# VC02.net
KiCad netlist of a schematic drawn in EAGLE
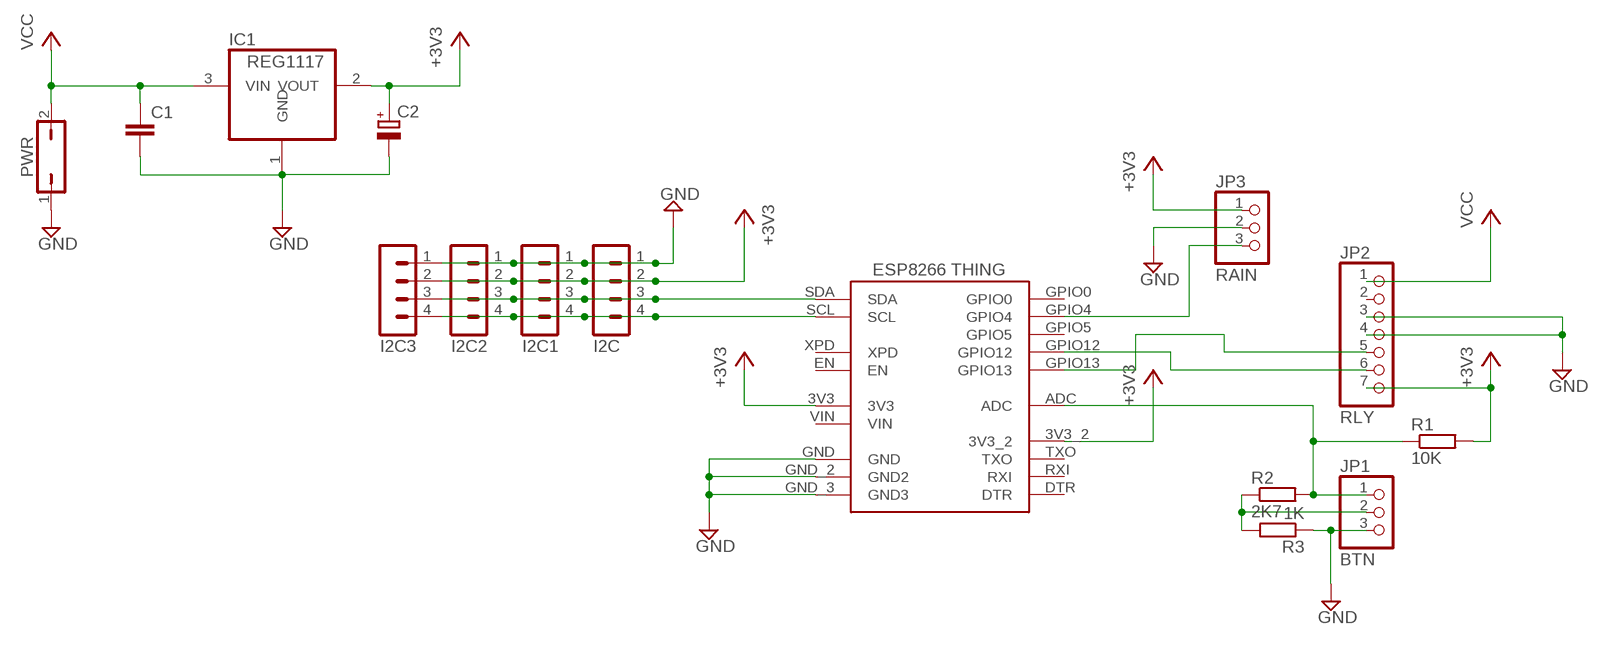
[diagram p0: schematic, sheet 1]

(export (version "E")
  (design (tool "Eeschema 10.0.6"))
  (components
    (comp (ref "C1")
      (value "C-EUC0603K")
      (footprint "eagle-import:C0603K")
      (fields (field (name "MF") "AVX") (field (name "MPN") "0603YC104K4T2A"))
      (libsource (lib "eagle-import") (part "C-EUC0603K"))
    )
    (comp (ref "C2")
      (value "CPOL-EUB")
      (footprint "eagle-import:PANASONIC_B")
      (fields (field (name "MF") "PANASONIC ELECTRONIC COMPONENTS") (field (name "MPN") "EEEFC1C220AR"))
      (libsource (lib "eagle-import") (part "CPOL-EUB"))
    )
    (comp (ref "I2C")
      (value "MA04-1")
      (footprint "eagle-import:MA04-1")
      (libsource (lib "eagle-import") (part "MA04-1"))
    )
    (comp (ref "I2C1")
      (value "MA04-1")
      (footprint "eagle-import:MA04-1")
      (libsource (lib "eagle-import") (part "MA04-1"))
    )
    (comp (ref "I2C2")
      (value "MA04-1")
      (footprint "eagle-import:MA04-1")
      (libsource (lib "eagle-import") (part "MA04-1"))
    )
    (comp (ref "I2C3")
      (value "MA04-1")
      (footprint "eagle-import:MA04-1")
      (libsource (lib "eagle-import") (part "MA04-1"))
    )
    (comp (ref "IC1")
      (value "REG1117")
      (footprint "eagle-import:SOT223")
      (fields
        (field (name "MF") "STMICROELECTRONICS")
        (field (name "MPN") "LD1117S33TR")
        (field (name "OC_FARNELL") "1202826")
      )
      (libsource (lib "eagle-import") (part "REG1117"))
    )
    (comp (ref "JP1")
      (value "BTN")
      (footprint "eagle-import:1X03")
      (libsource (lib "eagle-import") (part "PINHD-1X3"))
    )
    (comp (ref "JP2")
      (value "RLY")
      (footprint "eagle-import:1X07")
      (libsource (lib "eagle-import") (part "PINHD-1X7"))
    )
    (comp (ref "JP3")
      (value "RAIN")
      (footprint "eagle-import:1X03")
      (libsource (lib "eagle-import") (part "PINHD-1X3"))
    )
    (comp (ref "PWR")
      (value "JP1Q")
      (footprint "eagle-import:JP1")
      (fields (field (name "MF") "TE CONNECTIVITY / AMP") (field (name "MPN") "640452-2"))
      (libsource (lib "eagle-import") (part "JP1Q"))
    )
    (comp (ref "R1")
      (value "10K")
      (footprint "eagle-import:R0805")
      (fields (field (name "MF") "VISHAY DRALORIC") (field (name "MPN") "CRCW080510K0FKEA"))
      (libsource (lib "eagle-import") (part "R-EU_R0805"))
    )
    (comp (ref "R2")
      (value "2K7")
      (footprint "eagle-import:R0805")
      (fields (field (name "MF") "VISHAY DRALORIC") (field (name "MPN") "CRCW08052K70FKEA"))
      (libsource (lib "eagle-import") (part "R-EU_R0805"))
    )
    (comp (ref "R3")
      (value "1K")
      (footprint "eagle-import:R0805")
      (fields (field (name "MF") "VISHAY DRALORIC") (field (name "MPN") "CRCW08051K00FKEA"))
      (libsource (lib "eagle-import") (part "R-EU_R0805"))
    )
    (comp (ref "U$1")
      (value "ESP8266_THING")
      (footprint "eagle-import:ESP8266_THING")
      (libsource (lib "eagle-import") (part "ESP8266_THING"))
    )
  )
  (nets
    (net (code "1") (name "+3V3") (class "Default")
      (node (ref "C2") (pin "+") (pinfunction "+_+") (pintype "passive"))
      (node (ref "I2C") (pin "2") (pinfunction "2_2") (pintype "passive"))
      (node (ref "I2C1") (pin "2") (pinfunction "2_2") (pintype "passive"))
      (node (ref "I2C2") (pin "2") (pinfunction "2_2") (pintype "passive"))
      (node (ref "I2C3") (pin "2") (pinfunction "2_2") (pintype "passive"))
      (node (ref "IC1") (pin "2") (pinfunction "VOUT_2") (pintype "output"))
      (node (ref "JP2") (pin "7") (pinfunction "7_7") (pintype "passive"))
      (node (ref "JP3") (pin "1") (pinfunction "1_1") (pintype "passive"))
      (node (ref "R1") (pin "2") (pinfunction "2_2") (pintype "passive"))
      (node (ref "U$1") (pin "3V3") (pinfunction "3V3_3V3") (pintype "power_in"))
      (node (ref "U$1") (pin "3V3_2") (pinfunction "3V3_2_3V3_2") (pintype "power_in"))
    )
    (net (code "2") (name "/VIN") (class "Default")
      (node (ref "U$1") (pin "VIN") (pinfunction "VIN_VIN") (pintype "power_in"))
    )
    (net (code "3") (name "GND") (class "Default")
      (node (ref "C1") (pin "2") (pinfunction "2_2") (pintype "passive"))
      (node (ref "C2") (pin "-") (pinfunction "-_-") (pintype "passive"))
      (node (ref "I2C") (pin "1") (pinfunction "1_1") (pintype "passive"))
      (node (ref "I2C1") (pin "1") (pinfunction "1_1") (pintype "passive"))
      (node (ref "I2C2") (pin "1") (pinfunction "1_1") (pintype "passive"))
      (node (ref "I2C3") (pin "1") (pinfunction "1_1") (pintype "passive"))
      (node (ref "IC1") (pin "1") (pinfunction "GND_1") (pintype "power_in"))
      (node (ref "JP1") (pin "3") (pinfunction "3_3") (pintype "passive"))
      (node (ref "JP2") (pin "3") (pinfunction "3_3") (pintype "passive"))
      (node (ref "JP2") (pin "4") (pinfunction "4_4") (pintype "passive"))
      (node (ref "JP3") (pin "2") (pinfunction "2_2") (pintype "passive"))
      (node (ref "PWR") (pin "1") (pinfunction "1_1") (pintype "passive"))
      (node (ref "R3") (pin "1") (pinfunction "1_1") (pintype "passive"))
      (node (ref "U$1") (pin "GND") (pinfunction "GND_GND") (pintype "power_in"))
      (node (ref "U$1") (pin "GND_2") (pinfunction "GND2_GND_2") (pintype "power_in"))
      (node (ref "U$1") (pin "GND_3") (pinfunction "GND3_GND_3") (pintype "power_in"))
    )
    (net (code "4") (name "Net-(I2C-Pad3)") (class "Default")
      (node (ref "I2C") (pin "3") (pinfunction "3_3") (pintype "passive"))
      (node (ref "I2C1") (pin "3") (pinfunction "3_3") (pintype "passive"))
      (node (ref "I2C2") (pin "3") (pinfunction "3_3") (pintype "passive"))
      (node (ref "I2C3") (pin "3") (pinfunction "3_3") (pintype "passive"))
      (node (ref "U$1") (pin "SDA") (pinfunction "SDA_SDA") (pintype "bidirectional"))
    )
    (net (code "5") (name "Net-(I2C-Pad4)") (class "Default")
      (node (ref "I2C") (pin "4") (pinfunction "4_4") (pintype "passive"))
      (node (ref "I2C1") (pin "4") (pinfunction "4_4") (pintype "passive"))
      (node (ref "I2C2") (pin "4") (pinfunction "4_4") (pintype "passive"))
      (node (ref "I2C3") (pin "4") (pinfunction "4_4") (pintype "passive"))
      (node (ref "U$1") (pin "SCL") (pinfunction "SCL_SCL") (pintype "bidirectional"))
    )
    (net (code "6") (name "Net-(JP1-Pad1)") (class "Default")
      (node (ref "JP1") (pin "1") (pinfunction "1_1") (pintype "passive"))
      (node (ref "R1") (pin "1") (pinfunction "1_1") (pintype "passive"))
      (node (ref "R2") (pin "2") (pinfunction "2_2") (pintype "passive"))
      (node (ref "U$1") (pin "ADC") (pinfunction "ADC_ADC") (pintype "input"))
    )
    (net (code "7") (name "Net-(JP1-Pad2)") (class "Default")
      (node (ref "JP1") (pin "2") (pinfunction "2_2") (pintype "passive"))
      (node (ref "R2") (pin "1") (pinfunction "1_1") (pintype "passive"))
      (node (ref "R3") (pin "2") (pinfunction "2_2") (pintype "passive"))
    )
    (net (code "8") (name "Net-(JP2-Pad5)") (class "Default")
      (node (ref "JP2") (pin "5") (pinfunction "5_5") (pintype "passive"))
      (node (ref "U$1") (pin "GPIO13") (pinfunction "GPIO13_GPIO13") (pintype "bidirectional"))
    )
    (net (code "9") (name "Net-(JP2-Pad6)") (class "Default")
      (node (ref "JP2") (pin "6") (pinfunction "6_6") (pintype "passive"))
      (node (ref "U$1") (pin "GPIO12") (pinfunction "GPIO12_GPIO12") (pintype "bidirectional"))
    )
    (net (code "10") (name "Net-(JP3-Pad3)") (class "Default")
      (node (ref "JP3") (pin "3") (pinfunction "3_3") (pintype "passive"))
      (node (ref "U$1") (pin "GPIO4") (pinfunction "GPIO4_GPIO4") (pintype "bidirectional"))
    )
    (net (code "11") (name "VCC") (class "Default")
      (node (ref "C1") (pin "1") (pinfunction "1_1") (pintype "passive"))
      (node (ref "IC1") (pin "3") (pinfunction "VIN_3") (pintype "input"))
      (node (ref "JP2") (pin "1") (pinfunction "1_1") (pintype "passive"))
      (node (ref "PWR") (pin "2") (pinfunction "2_2") (pintype "passive"))
    )
    (net (code "12") (name "unconnected-(JP2-Pad2)") (class "Default")
      (node (ref "JP2") (pin "2") (pinfunction "2_2") (pintype "passive"))
    )
    (net (code "13") (name "unconnected-(U$1-PadDTR)") (class "Default")
      (node (ref "U$1") (pin "DTR") (pinfunction "DTR_DTR") (pintype "input"))
    )
    (net (code "14") (name "unconnected-(U$1-PadEN)") (class "Default")
      (node (ref "U$1") (pin "EN") (pinfunction "EN_EN") (pintype "bidirectional"))
    )
    (net (code "15") (name "unconnected-(U$1-PadGPIO0)") (class "Default")
      (node (ref "U$1") (pin "GPIO0") (pinfunction "GPIO0_GPIO0") (pintype "bidirectional"))
    )
    (net (code "16") (name "unconnected-(U$1-PadGPIO5)") (class "Default")
      (node (ref "U$1") (pin "GPIO5") (pinfunction "GPIO5_GPIO5") (pintype "bidirectional"))
    )
    (net (code "17") (name "unconnected-(U$1-PadRXI)") (class "Default")
      (node (ref "U$1") (pin "RXI") (pinfunction "RXI_RXI") (pintype "input"))
    )
    (net (code "18") (name "unconnected-(U$1-PadTXO)") (class "Default")
      (node (ref "U$1") (pin "TXO") (pinfunction "TXO_TXO") (pintype "output"))
    )
    (net (code "19") (name "unconnected-(U$1-PadXPD)") (class "Default")
      (node (ref "U$1") (pin "XPD") (pinfunction "XPD_XPD") (pintype "bidirectional"))
    )
  )
)
